# Circuito_el_trico.net
KiCad netlist of a schematic drawn in EAGLE
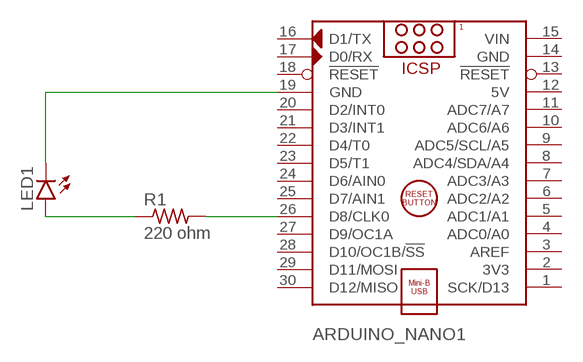
[diagram p0: schematic, sheet 1]

(export (version "E")
  (design (tool "Eeschema 10.0.6"))
  (components
    (comp (ref "ARDUINO_NANO1")
      (value "ARDUINO_NANO")
      (footprint "eagle-import:ARDUINO_NANO")
      (libsource (lib "eagle-import") (part "ARDUINO_NANO"))
    )
    (comp (ref "LED1")
      (value "LED-LUMILED")
      (footprint "eagle-import:LUMILED")
      (libsource (lib "eagle-import") (part "LED-LUMILED"))
    )
    (comp (ref "R1")
      (value "220 ohm")
      (footprint "eagle-import:0204V")
      (libsource (lib "eagle-import") (part "R-US_0204/2V"))
    )
  )
  (nets
    (net (code "1") (name "/5V") (class "Default")
      (node (ref "ARDUINO_NANO1") (pin "12") (pinfunction "5V_12") (pintype "power_in"))
    )
    (net (code "2") (name "/GND") (class "Default")
      (node (ref "ARDUINO_NANO1") (pin "14") (pinfunction "GND_14") (pintype "power_in"))
    )
    (net (code "3") (name "/VIN") (class "Default")
      (node (ref "ARDUINO_NANO1") (pin "15") (pinfunction "VIN_15") (pintype "power_in"))
    )
    (net (code "4") (name "Net-(ARDUINO_NANO1-D8{slash}CLK0)") (class "Default")
      (node (ref "ARDUINO_NANO1") (pin "26") (pinfunction "D8/CLK0_26") (pintype "bidirectional"))
      (node (ref "R1") (pin "2") (pinfunction "2_2") (pintype "passive"))
    )
    (net (code "5") (name "Net-(LED1-A)") (class "Default")
      (node (ref "LED1") (pin "2+") (pinfunction "A_2+") (pintype "passive"))
      (node (ref "R1") (pin "1") (pinfunction "1_1") (pintype "passive"))
    )
    (net (code "6") (name "Net-(LED1-C)") (class "Default")
      (node (ref "ARDUINO_NANO1") (pin "19") (pinfunction "GND_19") (pintype "power_in"))
      (node (ref "LED1") (pin "4-") (pinfunction "C_4-") (pintype "passive"))
    )
    (net (code "7") (name "unconnected-(ARDUINO_NANO1-3V3-Pad2)") (class "Default")
      (node (ref "ARDUINO_NANO1") (pin "2") (pinfunction "3V3_2") (pintype "output"))
    )
    (net (code "8") (name "unconnected-(ARDUINO_NANO1-ADC0{slash}A0-Pad4)") (class "Default")
      (node (ref "ARDUINO_NANO1") (pin "4") (pinfunction "ADC0/A0_4") (pintype "bidirectional"))
    )
    (net (code "9") (name "unconnected-(ARDUINO_NANO1-ADC1{slash}A1-Pad5)") (class "Default")
      (node (ref "ARDUINO_NANO1") (pin "5") (pinfunction "ADC1/A1_5") (pintype "bidirectional"))
    )
    (net (code "10") (name "unconnected-(ARDUINO_NANO1-ADC2{slash}A2-Pad6)") (class "Default")
      (node (ref "ARDUINO_NANO1") (pin "6") (pinfunction "ADC2/A2_6") (pintype "bidirectional"))
    )
    (net (code "11") (name "unconnected-(ARDUINO_NANO1-ADC3{slash}A3-Pad7)") (class "Default")
      (node (ref "ARDUINO_NANO1") (pin "7") (pinfunction "ADC3/A3_7") (pintype "bidirectional"))
    )
    (net (code "12") (name "unconnected-(ARDUINO_NANO1-ADC4{slash}SDA{slash}A4-Pad8)") (class "Default")
      (node (ref "ARDUINO_NANO1") (pin "8") (pinfunction "ADC4/SDA/A4_8") (pintype "bidirectional"))
    )
    (net (code "13") (name "unconnected-(ARDUINO_NANO1-ADC5{slash}SCL{slash}A5-Pad9)") (class "Default")
      (node (ref "ARDUINO_NANO1") (pin "9") (pinfunction "ADC5/SCL/A5_9") (pintype "bidirectional"))
    )
    (net (code "14") (name "unconnected-(ARDUINO_NANO1-ADC6{slash}A6-Pad10)") (class "Default")
      (node (ref "ARDUINO_NANO1") (pin "10") (pinfunction "ADC6/A6_10") (pintype "bidirectional"))
    )
    (net (code "15") (name "unconnected-(ARDUINO_NANO1-ADC7{slash}A7-Pad11)") (class "Default")
      (node (ref "ARDUINO_NANO1") (pin "11") (pinfunction "ADC7/A7_11") (pintype "bidirectional"))
    )
    (net (code "16") (name "unconnected-(ARDUINO_NANO1-AREF-Pad3)") (class "Default")
      (node (ref "ARDUINO_NANO1") (pin "3") (pinfunction "AREF_3") (pintype "input"))
    )
    (net (code "17") (name "unconnected-(ARDUINO_NANO1-D0{slash}RX-Pad17)") (class "Default")
      (node (ref "ARDUINO_NANO1") (pin "17") (pinfunction "D0/RX_17") (pintype "bidirectional"))
    )
    (net (code "18") (name "unconnected-(ARDUINO_NANO1-D1{slash}TX-Pad16)") (class "Default")
      (node (ref "ARDUINO_NANO1") (pin "16") (pinfunction "D1/TX_16") (pintype "bidirectional"))
    )
    (net (code "19") (name "unconnected-(ARDUINO_NANO1-D2{slash}INT0-Pad20)") (class "Default")
      (node (ref "ARDUINO_NANO1") (pin "20") (pinfunction "D2/INT0_20") (pintype "bidirectional"))
    )
    (net (code "20") (name "unconnected-(ARDUINO_NANO1-D3{slash}INT1-Pad21)") (class "Default")
      (node (ref "ARDUINO_NANO1") (pin "21") (pinfunction "D3/INT1_21") (pintype "bidirectional"))
    )
    (net (code "21") (name "unconnected-(ARDUINO_NANO1-D4{slash}T0-Pad22)") (class "Default")
      (node (ref "ARDUINO_NANO1") (pin "22") (pinfunction "D4/T0_22") (pintype "bidirectional"))
    )
    (net (code "22") (name "unconnected-(ARDUINO_NANO1-D5{slash}T1-Pad23)") (class "Default")
      (node (ref "ARDUINO_NANO1") (pin "23") (pinfunction "D5/T1_23") (pintype "bidirectional"))
    )
    (net (code "23") (name "unconnected-(ARDUINO_NANO1-D6{slash}AIN0-Pad24)") (class "Default")
      (node (ref "ARDUINO_NANO1") (pin "24") (pinfunction "D6/AIN0_24") (pintype "bidirectional"))
    )
    (net (code "24") (name "unconnected-(ARDUINO_NANO1-D7{slash}AIN1-Pad25)") (class "Default")
      (node (ref "ARDUINO_NANO1") (pin "25") (pinfunction "D7/AIN1_25") (pintype "bidirectional"))
    )
    (net (code "25") (name "unconnected-(ARDUINO_NANO1-D9{slash}OC1A-Pad27)") (class "Default")
      (node (ref "ARDUINO_NANO1") (pin "27") (pinfunction "D9/OC1A_27") (pintype "bidirectional"))
    )
    (net (code "26") (name "unconnected-(ARDUINO_NANO1-D10{slash}OC1B{slash}~{SS}-Pad28)") (class "Default")
      (node (ref "ARDUINO_NANO1") (pin "28") (pinfunction "D10/OC1B/~{SS}_28") (pintype "bidirectional"))
    )
    (net (code "27") (name "unconnected-(ARDUINO_NANO1-D11{slash}MOSI-Pad29)") (class "Default")
      (node (ref "ARDUINO_NANO1") (pin "29") (pinfunction "D11/MOSI_29") (pintype "bidirectional"))
    )
    (net (code "28") (name "unconnected-(ARDUINO_NANO1-D12{slash}MISO-Pad30)") (class "Default")
      (node (ref "ARDUINO_NANO1") (pin "30") (pinfunction "D12/MISO_30") (pintype "bidirectional"))
    )
    (net (code "29") (name "unconnected-(ARDUINO_NANO1-SCK{slash}D13-Pad1)") (class "Default")
      (node (ref "ARDUINO_NANO1") (pin "1") (pinfunction "SCK/D13_1") (pintype "bidirectional"))
    )
    (net (code "30") (name "unconnected-(ARDUINO_NANO1-~{RESET}-Pad13)") (class "Default")
      (node (ref "ARDUINO_NANO1") (pin "13") (pinfunction "~{RESET}_13") (pintype "input"))
    )
    (net (code "31") (name "unconnected-(ARDUINO_NANO1-~{RESET}-Pad18)") (class "Default")
      (node (ref "ARDUINO_NANO1") (pin "18") (pinfunction "~{RESET}_18") (pintype "input"))
    )
  )
)
